# AMU-S07-V00-AMSShutdown.net
KiCad netlist of a schematic drawn in Altium Designer
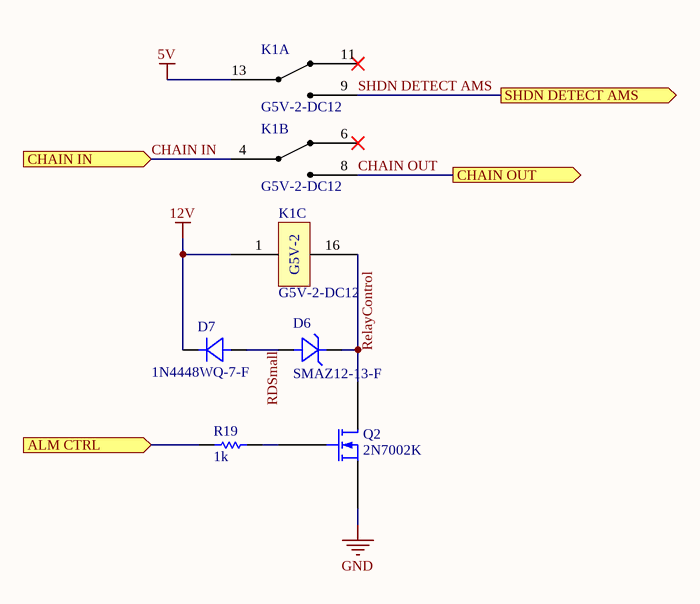
[diagram p0: AMU-S07-V00-AMSShutdown.SchDoc]

(export (version "E")
  (design (tool "Eeschema 10.0.6"))
  (components
    (comp (ref "D6")
      (value "SMAZ12-13-F")
      (footprint "SMA")
      (description "Zener Diode 12V 1W ±5% Surface Mount SMA")
      (fields (field (name "MANUFACTURER") "ON Semiconductor") (field (name "MPN") "MM3Z56VB"))
      (libsource (lib "QUTMS_DiodeLibrary") (part "SMAZ12-13-F"))
    )
    (comp (ref "D7")
      (value "1N4448WQ-7-F")
      (footprint "SMA")
      (description "Diode, SMD, 75V, 5%, 250mA, SOD123")
      (fields
        (field (name "MANUFACTURER") "ON Semiconductor / Fairchild")
        (field (name "MANUFACTURER PART NUMBER") "1N914BWS")
      )
      (libsource (lib "QUTMS_DiodeLibrary") (part "1N4448WQ-7-F"))
    )
    (comp (ref "K1")
      (value "G5V-2-DC12")
      (footprint "G5V-2")
      (description "General Purpose Relay DPDT (2 Form C) Through Hole, 12V, 2A")
      (libsource (lib "QUTMS_RelayLibrary") (part "G5V-2-DC12"))
    )
    (comp (ref "Q2")
      (value "2N7002K")
      (footprint "SOT-23-3")
      (description "N-Channel 60V 300mA (Ta) 350mW (Ta) Surface Mount SOT-23 (TO-236AB)")
      (libsource (lib "QUTMS_Transistors") (part "2N7002K"))
    )
    (comp (ref "R19")
      (value "1k")
      (footprint "Res_ThinFilm_0603")
      (description "Resistor, SMD, 1k, 0.1W, 5%, 0603")
      (libsource (lib "StandardResistors") (part "1k 5% 0603"))
    )
  )
  (nets
    (net (code "1") (name "/ALM CTRL") (class "Default")
      (node (ref "R19") (pin "1") (pinfunction "1_1") (pintype "passive"))
    )
    (net (code "2") (name "/CHAIN IN") (class "Default")
      (node (ref "K1") (pin "4") (pinfunction "4_4") (pintype "passive"))
    )
    (net (code "3") (name "/CHAIN OUT") (class "Default")
      (node (ref "K1") (pin "8") (pinfunction "8_8") (pintype "passive"))
    )
    (net (code "4") (name "/RDSmall") (class "Default")
      (node (ref "D6") (pin "A") (pinfunction "Anode_A") (pintype "passive"))
      (node (ref "D7") (pin "A") (pinfunction "Anode_A") (pintype "passive"))
    )
    (net (code "5") (name "/RelayControl") (class "Default")
      (node (ref "D6") (pin "K") (pinfunction "Cathode_K") (pintype "passive"))
      (node (ref "K1") (pin "16") (pinfunction "16_16") (pintype "passive"))
      (node (ref "Q2") (pin "D") (pinfunction "D_D") (pintype "passive"))
    )
    (net (code "6") (name "/SHDN DETECT AMS") (class "Default")
      (node (ref "K1") (pin "9") (pinfunction "9_9") (pintype "passive"))
    )
    (net (code "7") (name "5V") (class "Default")
      (node (ref "K1") (pin "13") (pinfunction "13_13") (pintype "passive"))
    )
    (net (code "8") (name "12V") (class "Default")
      (node (ref "D7") (pin "K") (pinfunction "Cathode_K") (pintype "passive"))
      (node (ref "K1") (pin "1") (pinfunction "1_1") (pintype "passive"))
    )
    (net (code "9") (name "GND") (class "Default")
      (node (ref "Q2") (pin "S") (pinfunction "S_S") (pintype "passive"))
    )
    (net (code "10") (name "Net-(Q2-PadG)") (class "Default")
      (node (ref "Q2") (pin "G") (pinfunction "G_G") (pintype "passive"))
      (node (ref "R19") (pin "2") (pinfunction "2_2") (pintype "passive"))
    )
    (net (code "11") (name "unconnected-(K1-Pad6)") (class "Default")
      (node (ref "K1") (pin "6") (pinfunction "6_6") (pintype "passive+no_connect"))
    )
    (net (code "12") (name "unconnected-(K1-Pad11)") (class "Default")
      (node (ref "K1") (pin "11") (pinfunction "11_11") (pintype "passive+no_connect"))
    )
  )
)
